# Alarms.net
KiCad netlist of a schematic drawn in Altium Designer
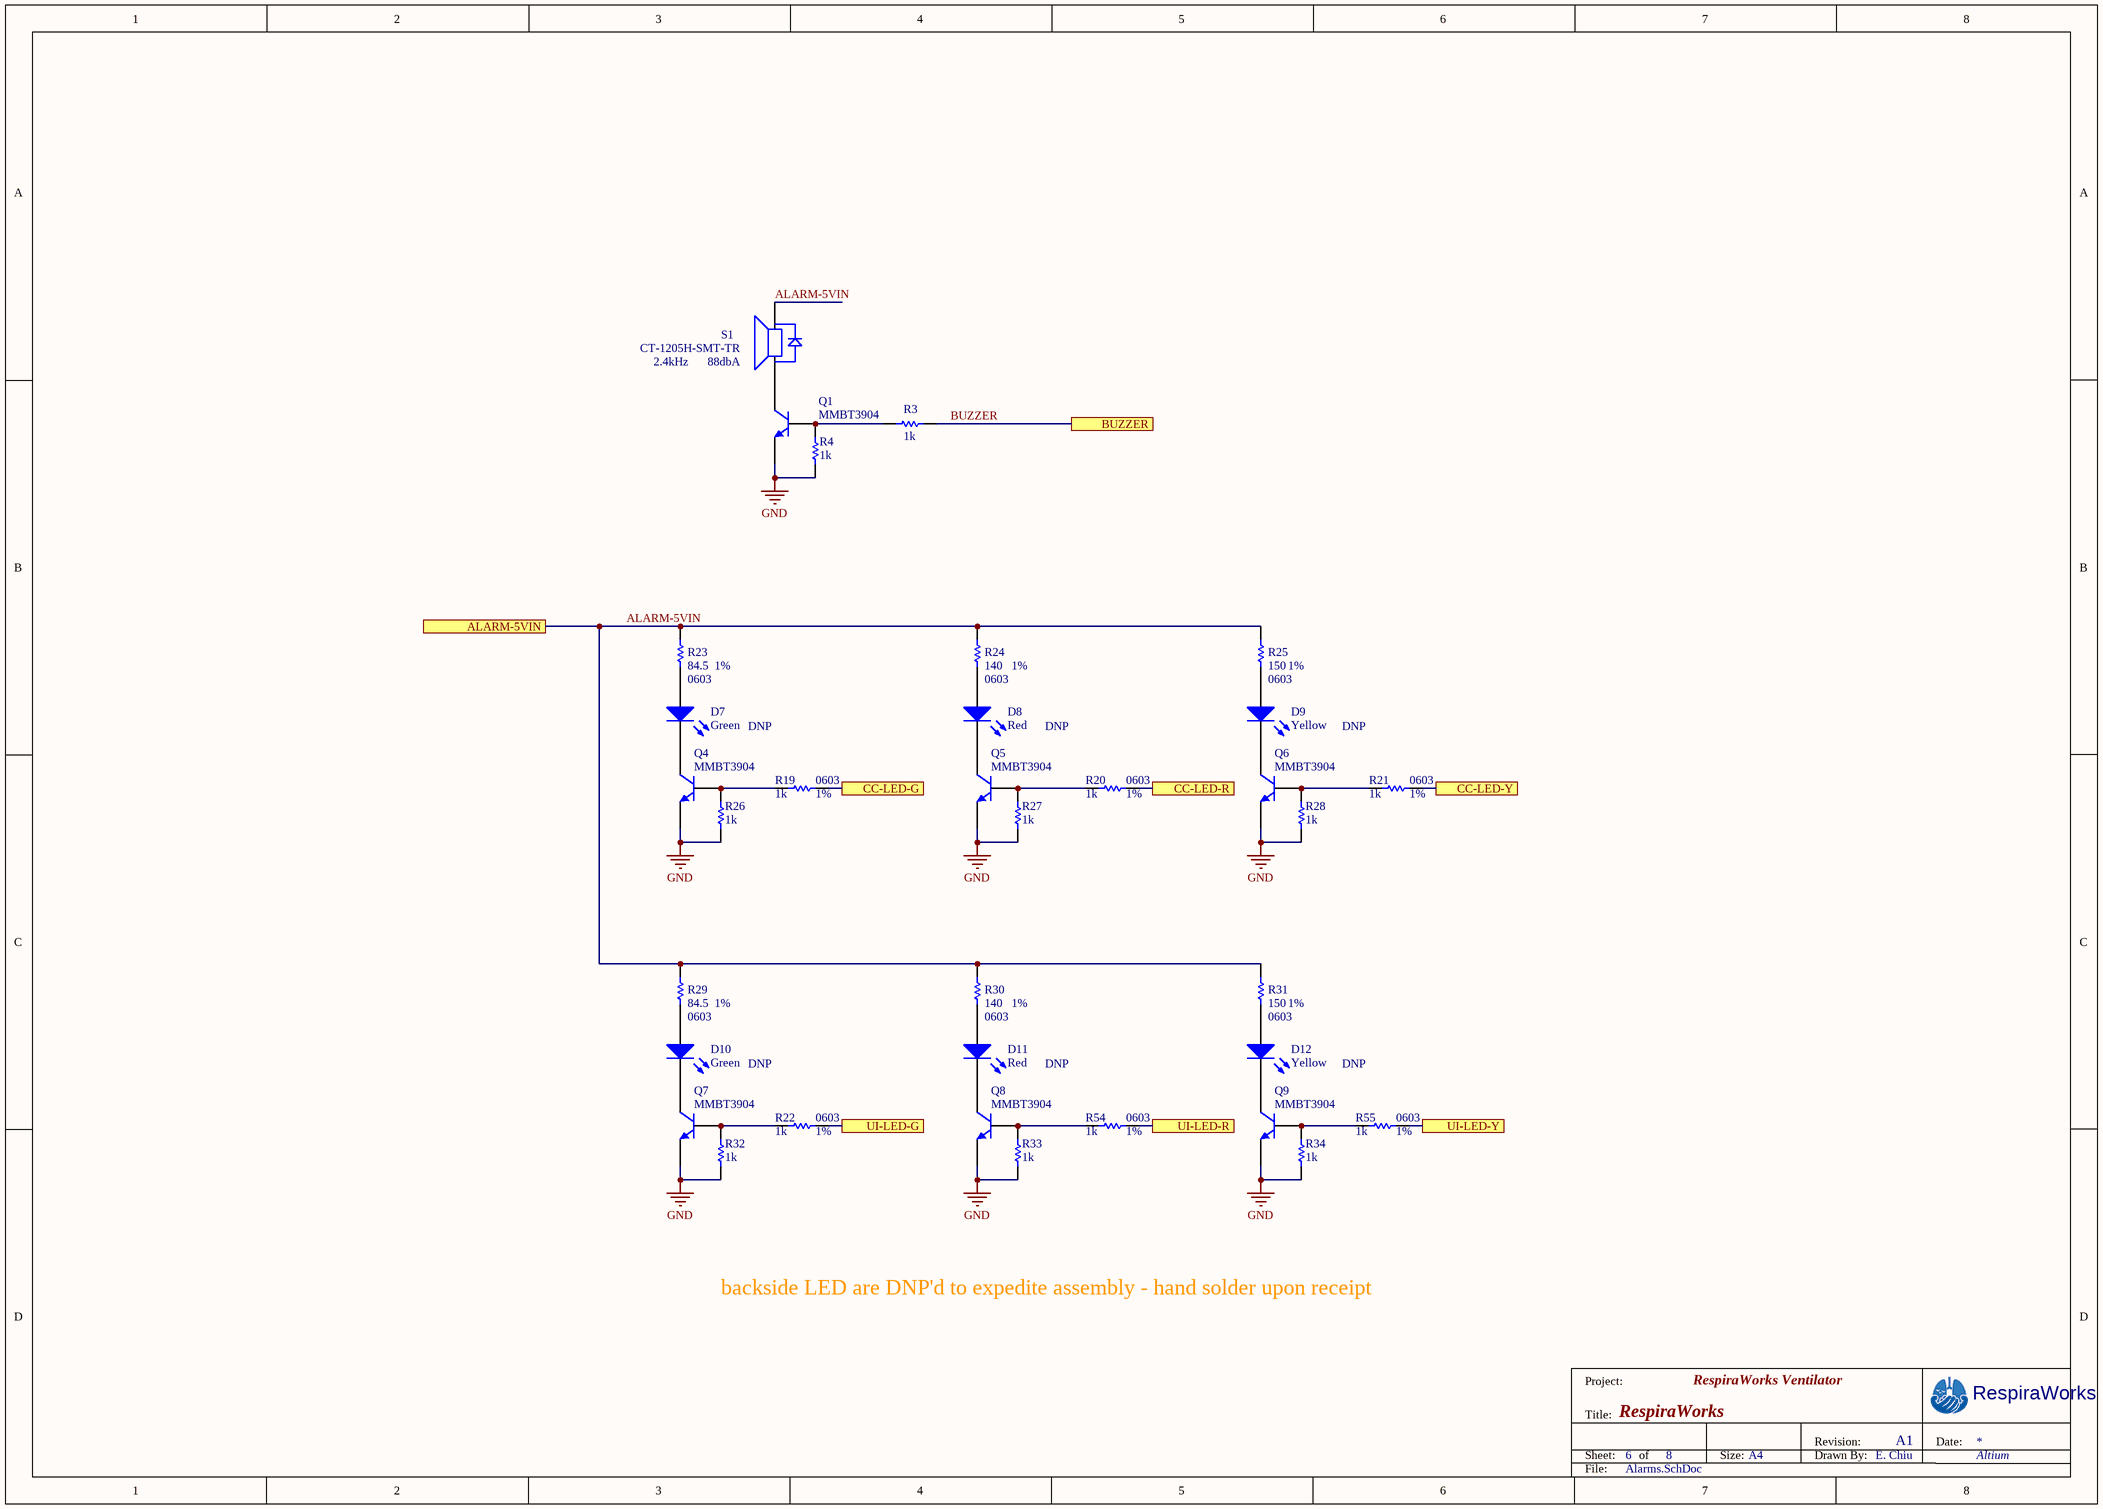
[diagram p0: Alarms.SchDoc]

(export (version "E")
  (design (tool "Eeschema 10.0.6"))
  (components
    (comp (ref "D7")
      (value "Green")
      (footprint "2-LED3528")
      (description "LED 3528 GREEN 500mcd")
      (fields
        (field (name "MANUFACTURER") "Kingbright")
        (field (name "DO NOT POPULATE") "DNP")
        (field (name "Comment") "LED 3528 GREEN 500MCD")
      )
      (libsource (lib "Kingbright") (part "LED 3528 GREEN 500MCD"))
    )
    (comp (ref "D8")
      (value "Red")
      (footprint "2-LED3528")
      (description "LED 3528 RED 450mcd")
      (fields
        (field (name "MANUFACTURER") "Kingbright")
        (field (name "DO NOT POPULATE") "DNP")
        (field (name "Comment") "LED 3528 RED 450MCD")
      )
      (libsource (lib "Kingbright") (part "LED 3528 RED 450MCD"))
    )
    (comp (ref "D9")
      (value "Yellow")
      (footprint "2-LED3528")
      (description "LED 3528 YELLOW 450mcd")
      (fields
        (field (name "MANUFACTURER") "Kingbright")
        (field (name "DO NOT POPULATE") "DNP")
        (field (name "Comment") "LED 3528 YELLOW 450MCD")
      )
      (libsource (lib "Kingbright") (part "LED 3528 YELLOW 450MCD"))
    )
    (comp (ref "D10")
      (value "Green")
      (footprint "2-LED3528")
      (description "LED 3528 GREEN 500mcd")
      (fields
        (field (name "MANUFACTURER") "Kingbright")
        (field (name "DO NOT POPULATE") "DNP")
        (field (name "Comment") "LED 3528 GREEN 500MCD")
      )
      (libsource (lib "Kingbright") (part "LED 3528 GREEN 500MCD"))
    )
    (comp (ref "D11")
      (value "Red")
      (footprint "2-LED3528")
      (description "LED 3528 RED 450mcd")
      (fields
        (field (name "MANUFACTURER") "Kingbright")
        (field (name "DO NOT POPULATE") "DNP")
        (field (name "Comment") "LED 3528 RED 450MCD")
      )
      (libsource (lib "Kingbright") (part "LED 3528 RED 450MCD"))
    )
    (comp (ref "D12")
      (value "Yellow")
      (footprint "2-LED3528")
      (description "LED 3528 YELLOW 450mcd")
      (fields
        (field (name "MANUFACTURER") "Kingbright")
        (field (name "DO NOT POPULATE") "DNP")
        (field (name "Comment") "LED 3528 YELLOW 450MCD")
      )
      (libsource (lib "Kingbright") (part "LED 3528 YELLOW 450MCD"))
    )
    (comp (ref "Q1")
      (value "MMBT3904")
      (footprint "3-SOT23")
      (description "Transistor, BJT NPN, General Purpose 40V")
      (fields (field (name "MANUFACTURER") "Fairchild") (field (name "MANUFACTURER P/N") "MMBT3904"))
      (libsource (lib "fairchild") (part "MMBT3904"))
    )
    (comp (ref "Q4")
      (value "MMBT3904")
      (footprint "3-SOT23")
      (description "Transistor, BJT NPN, General Purpose 40V")
      (fields (field (name "MANUFACTURER") "Fairchild") (field (name "MANUFACTURER P/N") "MMBT3904"))
      (libsource (lib "fairchild") (part "MMBT3904"))
    )
    (comp (ref "Q5")
      (value "MMBT3904")
      (footprint "3-SOT23")
      (description "Transistor, BJT NPN, General Purpose 40V")
      (fields (field (name "MANUFACTURER") "Fairchild") (field (name "MANUFACTURER P/N") "MMBT3904"))
      (libsource (lib "fairchild") (part "MMBT3904"))
    )
    (comp (ref "Q6")
      (value "MMBT3904")
      (footprint "3-SOT23")
      (description "Transistor, BJT NPN, General Purpose 40V")
      (fields (field (name "MANUFACTURER") "Fairchild") (field (name "MANUFACTURER P/N") "MMBT3904"))
      (libsource (lib "fairchild") (part "MMBT3904"))
    )
    (comp (ref "Q7")
      (value "MMBT3904")
      (footprint "3-SOT23")
      (description "Transistor, BJT NPN, General Purpose 40V")
      (fields (field (name "MANUFACTURER") "Fairchild") (field (name "MANUFACTURER P/N") "MMBT3904"))
      (libsource (lib "fairchild") (part "MMBT3904"))
    )
    (comp (ref "Q8")
      (value "MMBT3904")
      (footprint "3-SOT23")
      (description "Transistor, BJT NPN, General Purpose 40V")
      (fields (field (name "MANUFACTURER") "Fairchild") (field (name "MANUFACTURER P/N") "MMBT3904"))
      (libsource (lib "fairchild") (part "MMBT3904"))
    )
    (comp (ref "Q9")
      (value "MMBT3904")
      (footprint "3-SOT23")
      (description "Transistor, BJT NPN, General Purpose 40V")
      (fields (field (name "MANUFACTURER") "Fairchild") (field (name "MANUFACTURER P/N") "MMBT3904"))
      (libsource (lib "fairchild") (part "MMBT3904"))
    )
    (comp (ref "R3")
      (value "1k")
      (footprint "RES0603")
      (description "Res 0603")
      (fields (field (name "MANUFACTURER") "Yageo") (field (name "Comment") "RES 0603"))
      (libsource (lib "generic") (part "RES 0603"))
    )
    (comp (ref "R4")
      (value "1k")
      (footprint "RES0603")
      (description "Res 0603")
      (fields (field (name "MANUFACTURER") "Yageo") (field (name "Comment") "RES 0603"))
      (libsource (lib "generic") (part "RES 0603"))
    )
    (comp (ref "R19")
      (value "1k")
      (footprint "RES0603")
      (description "Res 0603")
      (fields
        (field (name "MANUFACTURER") "Yageo")
        (field (name "PCB PACKAGE") "0603")
        (field (name "TOLERANCE") "1%")
        (field (name "Comment") "RES 0603")
      )
      (libsource (lib "generic") (part "RES 0603"))
    )
    (comp (ref "R20")
      (value "1k")
      (footprint "RES0603")
      (description "Res 0603")
      (fields
        (field (name "MANUFACTURER") "Yageo")
        (field (name "PCB PACKAGE") "0603")
        (field (name "TOLERANCE") "1%")
        (field (name "Comment") "RES 0603")
      )
      (libsource (lib "generic") (part "RES 0603"))
    )
    (comp (ref "R21")
      (value "1k")
      (footprint "RES0603")
      (description "Res 0603")
      (fields
        (field (name "MANUFACTURER") "Yageo")
        (field (name "PCB PACKAGE") "0603")
        (field (name "TOLERANCE") "1%")
        (field (name "Comment") "RES 0603")
      )
      (libsource (lib "generic") (part "RES 0603"))
    )
    (comp (ref "R22")
      (value "1k")
      (footprint "RES0603")
      (description "Res 0603")
      (fields
        (field (name "MANUFACTURER") "Yageo")
        (field (name "PCB PACKAGE") "0603")
        (field (name "TOLERANCE") "1%")
        (field (name "Comment") "RES 0603")
      )
      (libsource (lib "generic") (part "RES 0603"))
    )
    (comp (ref "R23")
      (value "84.5")
      (footprint "RES0603")
      (description "Res 0603")
      (fields
        (field (name "MANUFACTURER") "Yageo")
        (field (name "PCB PACKAGE") "0603")
        (field (name "TOLERANCE") "1%")
        (field (name "Comment") "RES 0603")
      )
      (libsource (lib "generic") (part "RES 0603"))
    )
    (comp (ref "R24")
      (value "140")
      (footprint "RES0603")
      (description "Res 0603")
      (fields
        (field (name "MANUFACTURER") "Yageo")
        (field (name "PCB PACKAGE") "0603")
        (field (name "TOLERANCE") "1%")
        (field (name "Comment") "RES 0603")
      )
      (libsource (lib "generic") (part "RES 0603"))
    )
    (comp (ref "R25")
      (value "150")
      (footprint "RES0603")
      (description "Res 0603")
      (fields
        (field (name "MANUFACTURER") "Yageo")
        (field (name "PCB PACKAGE") "0603")
        (field (name "TOLERANCE") "1%")
        (field (name "Comment") "RES 0603")
      )
      (libsource (lib "generic") (part "RES 0603"))
    )
    (comp (ref "R26")
      (value "1k")
      (footprint "RES0603")
      (description "Res 0603")
      (fields (field (name "MANUFACTURER") "Yageo") (field (name "Comment") "RES 0603"))
      (libsource (lib "generic") (part "RES 0603"))
    )
    (comp (ref "R27")
      (value "1k")
      (footprint "RES0603")
      (description "Res 0603")
      (fields (field (name "MANUFACTURER") "Yageo") (field (name "Comment") "RES 0603"))
      (libsource (lib "generic") (part "RES 0603"))
    )
    (comp (ref "R28")
      (value "1k")
      (footprint "RES0603")
      (description "Res 0603")
      (fields (field (name "MANUFACTURER") "Yageo") (field (name "Comment") "RES 0603"))
      (libsource (lib "generic") (part "RES 0603"))
    )
    (comp (ref "R29")
      (value "84.5")
      (footprint "RES0603")
      (description "Res 0603")
      (fields
        (field (name "MANUFACTURER") "Yageo")
        (field (name "PCB PACKAGE") "0603")
        (field (name "TOLERANCE") "1%")
        (field (name "Comment") "RES 0603")
      )
      (libsource (lib "generic") (part "RES 0603"))
    )
    (comp (ref "R30")
      (value "140")
      (footprint "RES0603")
      (description "Res 0603")
      (fields
        (field (name "MANUFACTURER") "Yageo")
        (field (name "PCB PACKAGE") "0603")
        (field (name "TOLERANCE") "1%")
        (field (name "Comment") "RES 0603")
      )
      (libsource (lib "generic") (part "RES 0603"))
    )
    (comp (ref "R31")
      (value "150")
      (footprint "RES0603")
      (description "Res 0603")
      (fields
        (field (name "MANUFACTURER") "Yageo")
        (field (name "PCB PACKAGE") "0603")
        (field (name "TOLERANCE") "1%")
        (field (name "Comment") "RES 0603")
      )
      (libsource (lib "generic") (part "RES 0603"))
    )
    (comp (ref "R32")
      (value "1k")
      (footprint "RES0603")
      (description "Res 0603")
      (fields (field (name "MANUFACTURER") "Yageo") (field (name "Comment") "RES 0603"))
      (libsource (lib "generic") (part "RES 0603"))
    )
    (comp (ref "R33")
      (value "1k")
      (footprint "RES0603")
      (description "Res 0603")
      (fields (field (name "MANUFACTURER") "Yageo") (field (name "Comment") "RES 0603"))
      (libsource (lib "generic") (part "RES 0603"))
    )
    (comp (ref "R34")
      (value "1k")
      (footprint "RES0603")
      (description "Res 0603")
      (fields (field (name "MANUFACTURER") "Yageo") (field (name "Comment") "RES 0603"))
      (libsource (lib "generic") (part "RES 0603"))
    )
    (comp (ref "R54")
      (value "1k")
      (footprint "RES0603")
      (description "Res 0603")
      (fields
        (field (name "MANUFACTURER") "Yageo")
        (field (name "PCB PACKAGE") "0603")
        (field (name "TOLERANCE") "1%")
        (field (name "Comment") "RES 0603")
      )
      (libsource (lib "generic") (part "RES 0603"))
    )
    (comp (ref "R55")
      (value "1k")
      (footprint "RES0603")
      (description "Res 0603")
      (fields
        (field (name "MANUFACTURER") "Yageo")
        (field (name "PCB PACKAGE") "0603")
        (field (name "TOLERANCE") "1%")
        (field (name "Comment") "RES 0603")
      )
      (libsource (lib "generic") (part "RES 0603"))
    )
    (comp (ref "S1")
      (value "88dbA")
      (footprint "CT-1205H-SMT-TR")
      (fields
        (field (name "MANUFACTURER P/N") "CT-1205H-SMT-TR")
        (field (name "MANUFACTURER") "CUI")
        (field (name "FREQUENCY") "2.4kHz")
        (field (name "Comment") "CT-1205H-SMT-TR")
      )
      (libsource (lib "cui") (part "CT-1205H-SMT-TR"))
    )
  )
  (nets
    (net (code "1") (name "/ALARM-5VIN") (class "Default")
      (node (ref "R23") (pin "2") (pinfunction "2_2") (pintype "passive"))
      (node (ref "R24") (pin "2") (pinfunction "2_2") (pintype "passive"))
      (node (ref "R25") (pin "2") (pinfunction "2_2") (pintype "passive"))
      (node (ref "R29") (pin "2") (pinfunction "2_2") (pintype "passive"))
      (node (ref "R30") (pin "2") (pinfunction "2_2") (pintype "passive"))
      (node (ref "R31") (pin "2") (pinfunction "2_2") (pintype "passive"))
      (node (ref "S1") (pin "2") (pinfunction "2_2") (pintype "passive"))
    )
    (net (code "2") (name "/BUZZER") (class "Default")
      (node (ref "R3") (pin "2") (pinfunction "2_2") (pintype "passive"))
    )
    (net (code "3") (name "/CC-LED-G") (class "Default")
      (node (ref "R19") (pin "1") (pinfunction "1_1") (pintype "passive"))
    )
    (net (code "4") (name "/CC-LED-R") (class "Default")
      (node (ref "R20") (pin "1") (pinfunction "1_1") (pintype "passive"))
    )
    (net (code "5") (name "/CC-LED-Y") (class "Default")
      (node (ref "R21") (pin "1") (pinfunction "1_1") (pintype "passive"))
    )
    (net (code "6") (name "/UI-LED-G") (class "Default")
      (node (ref "R22") (pin "1") (pinfunction "1_1") (pintype "passive"))
    )
    (net (code "7") (name "/UI-LED-R") (class "Default")
      (node (ref "R54") (pin "1") (pinfunction "1_1") (pintype "passive"))
    )
    (net (code "8") (name "/UI-LED-Y") (class "Default")
      (node (ref "R55") (pin "1") (pinfunction "1_1") (pintype "passive"))
    )
    (net (code "9") (name "GND") (class "Default")
      (node (ref "Q1") (pin "2") (pinfunction "E_2") (pintype "passive"))
      (node (ref "Q4") (pin "2") (pinfunction "E_2") (pintype "passive"))
      (node (ref "Q5") (pin "2") (pinfunction "E_2") (pintype "passive"))
      (node (ref "Q6") (pin "2") (pinfunction "E_2") (pintype "passive"))
      (node (ref "Q7") (pin "2") (pinfunction "E_2") (pintype "passive"))
      (node (ref "Q8") (pin "2") (pinfunction "E_2") (pintype "passive"))
      (node (ref "Q9") (pin "2") (pinfunction "E_2") (pintype "passive"))
      (node (ref "R26") (pin "1") (pinfunction "1_1") (pintype "passive"))
      (node (ref "R27") (pin "1") (pinfunction "1_1") (pintype "passive"))
      (node (ref "R28") (pin "1") (pinfunction "1_1") (pintype "passive"))
      (node (ref "R32") (pin "1") (pinfunction "1_1") (pintype "passive"))
      (node (ref "R33") (pin "1") (pinfunction "1_1") (pintype "passive"))
      (node (ref "R34") (pin "1") (pinfunction "1_1") (pintype "passive"))
      (node (ref "R4") (pin "1") (pinfunction "1_1") (pintype "passive"))
    )
    (net (code "10") (name "Net-(D7-A)") (class "Default")
      (node (ref "D7") (pin "2") (pinfunction "A_2") (pintype "passive"))
      (node (ref "R23") (pin "1") (pinfunction "1_1") (pintype "passive"))
    )
    (net (code "11") (name "Net-(D7-K)") (class "Default")
      (node (ref "D7") (pin "1") (pinfunction "K_1") (pintype "passive"))
      (node (ref "Q4") (pin "3") (pinfunction "C_3") (pintype "passive"))
    )
    (net (code "12") (name "Net-(D8-A)") (class "Default")
      (node (ref "D8") (pin "2") (pinfunction "A_2") (pintype "passive"))
      (node (ref "R24") (pin "1") (pinfunction "1_1") (pintype "passive"))
    )
    (net (code "13") (name "Net-(D8-K)") (class "Default")
      (node (ref "D8") (pin "1") (pinfunction "K_1") (pintype "passive"))
      (node (ref "Q5") (pin "3") (pinfunction "C_3") (pintype "passive"))
    )
    (net (code "14") (name "Net-(D9-A)") (class "Default")
      (node (ref "D9") (pin "2") (pinfunction "A_2") (pintype "passive"))
      (node (ref "R25") (pin "1") (pinfunction "1_1") (pintype "passive"))
    )
    (net (code "15") (name "Net-(D9-K)") (class "Default")
      (node (ref "D9") (pin "1") (pinfunction "K_1") (pintype "passive"))
      (node (ref "Q6") (pin "3") (pinfunction "C_3") (pintype "passive"))
    )
    (net (code "16") (name "Net-(D10-A)") (class "Default")
      (node (ref "D10") (pin "2") (pinfunction "A_2") (pintype "passive"))
      (node (ref "R29") (pin "1") (pinfunction "1_1") (pintype "passive"))
    )
    (net (code "17") (name "Net-(D10-K)") (class "Default")
      (node (ref "D10") (pin "1") (pinfunction "K_1") (pintype "passive"))
      (node (ref "Q7") (pin "3") (pinfunction "C_3") (pintype "passive"))
    )
    (net (code "18") (name "Net-(D11-A)") (class "Default")
      (node (ref "D11") (pin "2") (pinfunction "A_2") (pintype "passive"))
      (node (ref "R30") (pin "1") (pinfunction "1_1") (pintype "passive"))
    )
    (net (code "19") (name "Net-(D11-K)") (class "Default")
      (node (ref "D11") (pin "1") (pinfunction "K_1") (pintype "passive"))
      (node (ref "Q8") (pin "3") (pinfunction "C_3") (pintype "passive"))
    )
    (net (code "20") (name "Net-(D12-A)") (class "Default")
      (node (ref "D12") (pin "2") (pinfunction "A_2") (pintype "passive"))
      (node (ref "R31") (pin "1") (pinfunction "1_1") (pintype "passive"))
    )
    (net (code "21") (name "Net-(D12-K)") (class "Default")
      (node (ref "D12") (pin "1") (pinfunction "K_1") (pintype "passive"))
      (node (ref "Q9") (pin "3") (pinfunction "C_3") (pintype "passive"))
    )
    (net (code "22") (name "Net-(Q1-B)") (class "Default")
      (node (ref "Q1") (pin "1") (pinfunction "B_1") (pintype "passive"))
      (node (ref "R3") (pin "1") (pinfunction "1_1") (pintype "passive"))
      (node (ref "R4") (pin "2") (pinfunction "2_2") (pintype "passive"))
    )
    (net (code "23") (name "Net-(Q1-C)") (class "Default")
      (node (ref "Q1") (pin "3") (pinfunction "C_3") (pintype "passive"))
      (node (ref "S1") (pin "1") (pinfunction "1_1") (pintype "passive"))
    )
    (net (code "24") (name "Net-(Q4-B)") (class "Default")
      (node (ref "Q4") (pin "1") (pinfunction "B_1") (pintype "passive"))
      (node (ref "R19") (pin "2") (pinfunction "2_2") (pintype "passive"))
      (node (ref "R26") (pin "2") (pinfunction "2_2") (pintype "passive"))
    )
    (net (code "25") (name "Net-(Q5-B)") (class "Default")
      (node (ref "Q5") (pin "1") (pinfunction "B_1") (pintype "passive"))
      (node (ref "R20") (pin "2") (pinfunction "2_2") (pintype "passive"))
      (node (ref "R27") (pin "2") (pinfunction "2_2") (pintype "passive"))
    )
    (net (code "26") (name "Net-(Q6-B)") (class "Default")
      (node (ref "Q6") (pin "1") (pinfunction "B_1") (pintype "passive"))
      (node (ref "R21") (pin "2") (pinfunction "2_2") (pintype "passive"))
      (node (ref "R28") (pin "2") (pinfunction "2_2") (pintype "passive"))
    )
    (net (code "27") (name "Net-(Q7-B)") (class "Default")
      (node (ref "Q7") (pin "1") (pinfunction "B_1") (pintype "passive"))
      (node (ref "R22") (pin "2") (pinfunction "2_2") (pintype "passive"))
      (node (ref "R32") (pin "2") (pinfunction "2_2") (pintype "passive"))
    )
    (net (code "28") (name "Net-(Q8-B)") (class "Default")
      (node (ref "Q8") (pin "1") (pinfunction "B_1") (pintype "passive"))
      (node (ref "R33") (pin "2") (pinfunction "2_2") (pintype "passive"))
      (node (ref "R54") (pin "2") (pinfunction "2_2") (pintype "passive"))
    )
    (net (code "29") (name "Net-(Q9-B)") (class "Default")
      (node (ref "Q9") (pin "1") (pinfunction "B_1") (pintype "passive"))
      (node (ref "R34") (pin "2") (pinfunction "2_2") (pintype "passive"))
      (node (ref "R55") (pin "2") (pinfunction "2_2") (pintype "passive"))
    )
  )
)
